# Power_Supplies.net
KiCad netlist of a schematic drawn in Altium Designer
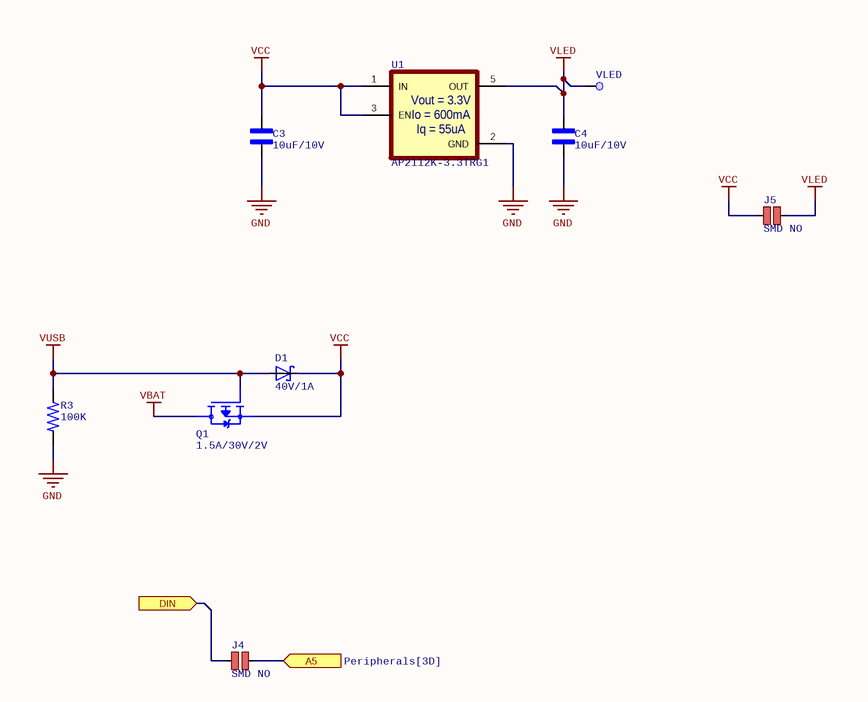
[diagram p0: Power_Supplies.SchDoc]

(export (version "E")
  (design (tool "Eeschema 10.0.6"))
  (components
    (comp (ref "C3")
      (value "10uF/10V")
      (footprint "C0603")
      (description "MLCC 10uF 10V X5R 20% 0603")
      (fields
        (field (name "MANUFACTURER") "Samsung")
        (field (name "MANUFACTURER PART NUMBER") "CL10A106MP8NNND")
      )
      (libsource (lib "Capacitors") (part "C0603 10uF/10V"))
    )
    (comp (ref "C4")
      (value "10uF/10V")
      (footprint "C0603")
      (description "MLCC 10uF 10V X5R 20% 0603")
      (fields
        (field (name "MANUFACTURER") "Samsung")
        (field (name "MANUFACTURER PART NUMBER") "CL10A106MP8NNND")
      )
      (libsource (lib "Capacitors") (part "C0603 10uF/10V"))
    )
    (comp (ref "D1")
      (value "40V/1A")
      (footprint "SMA-2")
      (description "SS14 Series 500 mV 1 A 40 V Max Reverse Voltage Schottky Rectifier - DO-214AC")
      (fields
        (field (name "MANUFACTURER") "ON Semiconductor / Fairchild")
        (field (name "MANUFACTURER PART NUMBER") "SS14")
      )
      (libsource (lib "Diodes") (part "SS14"))
    )
    (comp (ref "J4")
      (value "SMD NO")
      (footprint "JUMPER_SMD_NO")
      (libsource (lib "Jumpers") (part "JUMPER_SMD_NO"))
    )
    (comp (ref "J5")
      (value "SMD NO")
      (footprint "JUMPER_SMD_NO")
      (libsource (lib "Jumpers") (part "JUMPER_SMD_NO"))
    )
    (comp (ref "Q1")
      (value "1.5A/30V/2V")
      (footprint "SOT-23-3")
      (description "MOSFET P-Ch -30V -1.5A SOT-23-3")
      (fields (field (name "MANUFACTURER") "Infineon") (field (name "MANUFACTURER PART NUMBER") "BSS314PE"))
      (libsource (lib "DiscreteSemi") (part "MOSFET P-CH 30V/1.5A BSS314"))
    )
    (comp (ref "R3")
      (value "100K")
      (footprint "R0603")
      (description "RES 0603 100K OHM 1% 1/10W")
      (fields
        (field (name "MANUFACTURER") "Yageo")
        (field (name "MANUFACTURER PART NUMBER") "RC0603FR-07100KL")
      )
      (libsource (lib "Resistors") (part "R0603 100K"))
    )
    (comp (ref "U1")
      (value "AP2112K-3.3TRG1")
      (footprint "SOT-25-5")
      (description "IC REG LINEAR 3.3V 600MA SOT25")
      (fields (field (name "MANUFACTURER") "Diodes"))
      (libsource (lib "IC Power") (part "AP2112K-3.3TRG1"))
    )
    (comp (ref "VLED")
      (value "Test point 1.2mm")
      (footprint "TEST_POINT_1.2MM")
      (description "SMD test point")
      (libsource (lib "Connectors") (part "Test point"))
    )
  )
  (nets
    (net (code "1") (name "/A5") (class "Default")
      (node (ref "J4") (pin "2") (pinfunction "2_2") (pintype "passive"))
    )
    (net (code "2") (name "/DIN") (class "Default")
      (node (ref "J4") (pin "1") (pinfunction "1_1") (pintype "passive"))
    )
    (net (code "3") (name "GND") (class "Default")
      (node (ref "C3") (pin "2") (pinfunction "2_2") (pintype "passive"))
      (node (ref "C4") (pin "2") (pinfunction "2_2") (pintype "passive"))
      (node (ref "R3") (pin "2") (pinfunction "2_2") (pintype "passive"))
      (node (ref "U1") (pin "2") (pinfunction "GND_2") (pintype "power_in"))
    )
    (net (code "4") (name "VBAT") (class "Default")
      (node (ref "Q1") (pin "3") (pinfunction "D_3") (pintype "passive"))
    )
    (net (code "5") (name "VCC") (class "Default")
      (node (ref "C3") (pin "1") (pinfunction "1_1") (pintype "passive"))
      (node (ref "D1") (pin "K") (pinfunction "K_K") (pintype "passive"))
      (node (ref "J5") (pin "1") (pinfunction "1_1") (pintype "passive"))
      (node (ref "Q1") (pin "2") (pinfunction "S_2") (pintype "passive"))
      (node (ref "U1") (pin "1") (pinfunction "IN_1") (pintype "power_in"))
      (node (ref "U1") (pin "3") (pinfunction "EN_3") (pintype "passive"))
    )
    (net (code "6") (name "VLED") (class "Default")
      (node (ref "C4") (pin "1") (pinfunction "1_1") (pintype "passive"))
      (node (ref "J5") (pin "2") (pinfunction "2_2") (pintype "passive"))
      (node (ref "U1") (pin "5") (pinfunction "OUT_5") (pintype "power_in"))
      (node (ref "VLED") (pin "1") (pinfunction "1_1") (pintype "passive"))
    )
    (net (code "7") (name "VUSB") (class "Default")
      (node (ref "D1") (pin "A") (pinfunction "A_A") (pintype "passive"))
      (node (ref "Q1") (pin "1") (pinfunction "G_1") (pintype "passive"))
      (node (ref "R3") (pin "1") (pinfunction "1_1") (pintype "passive"))
    )
  )
)
